# Desklamp_H180804_V1.net
KiCad netlist of a schematic drawn in EAGLE
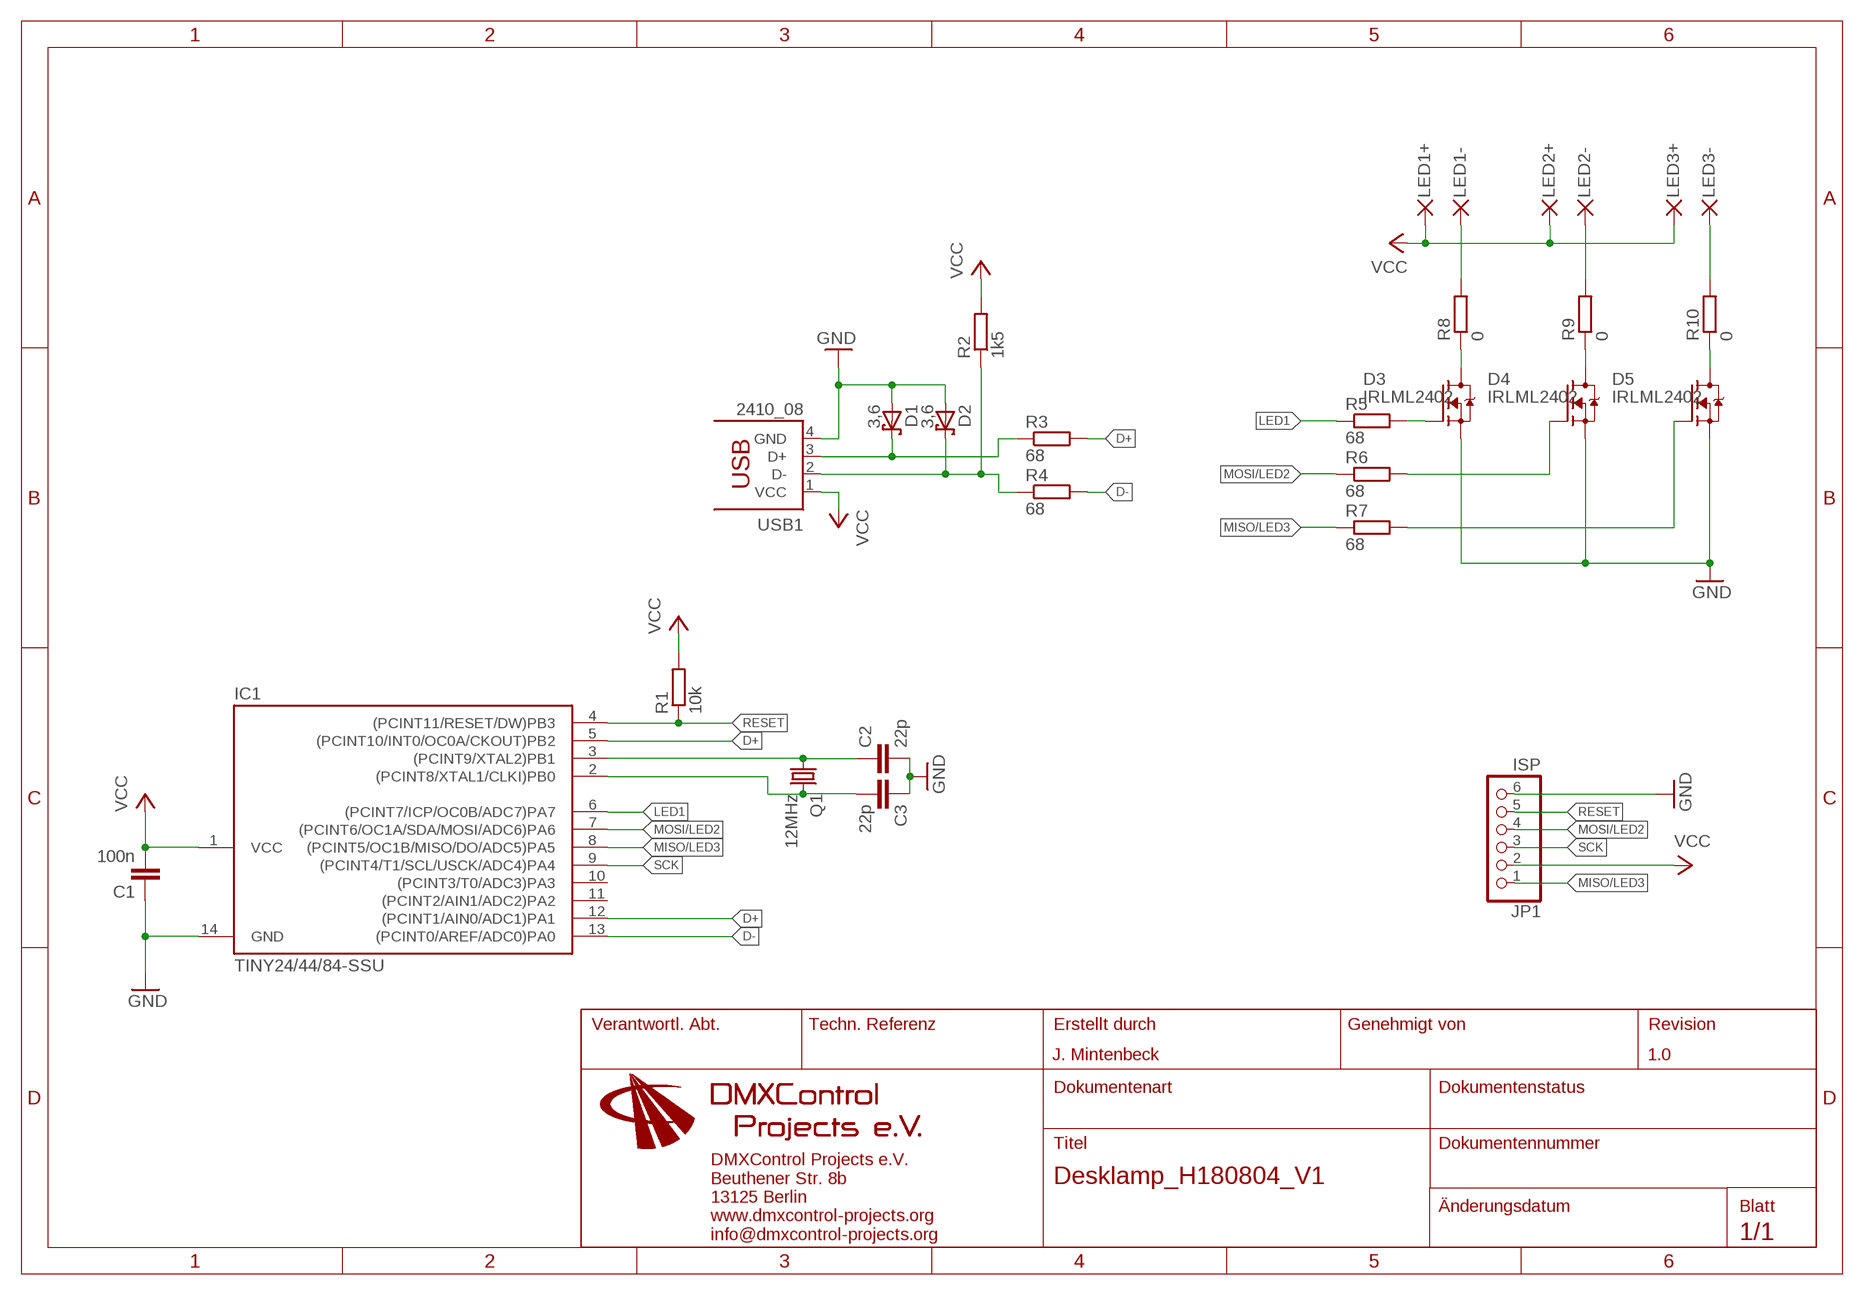
[diagram p0: schematic, sheet 1]

(export (version "E")
  (design (tool "Eeschema 10.0.6"))
  (components
    (comp (ref "C1")
      (value "100n")
      (footprint "eagle-import:C0805")
      (fields (field (name "PARTNO") "CC0805KRX7R9BB104"))
      (libsource (lib "eagle-import") (part "C-EUC0805"))
    )
    (comp (ref "C2")
      (value "22p")
      (footprint "eagle-import:C0805")
      (fields (field (name "PARTNO") "VVS-SMD COG 50 V 22 PF G0805"))
      (libsource (lib "eagle-import") (part "C-EUC0805"))
    )
    (comp (ref "C3")
      (value "22p")
      (footprint "eagle-import:C0805")
      (fields (field (name "PARTNO") "VVS-SMD COG 50 V 22 PF G0805"))
      (libsource (lib "eagle-import") (part "C-EUC0805"))
    )
    (comp (ref "D1")
      (value "3,6")
      (footprint "eagle-import:SOT23")
      (fields (field (name "PARTNO") "BZX84C3V6"))
      (libsource (lib "eagle-import") (part "BAS40"))
    )
    (comp (ref "D2")
      (value "3,6")
      (footprint "eagle-import:SOT23")
      (fields (field (name "PARTNO") "BZX84C3V6"))
      (libsource (lib "eagle-import") (part "BAS40"))
    )
    (comp (ref "D3")
      (value "IRLML2402")
      (footprint "eagle-import:SOT23")
      (fields (field (name "PARTNO") "IRLML2402PBF"))
      (libsource (lib "eagle-import") (part "IRLML2402"))
    )
    (comp (ref "D4")
      (value "IRLML2402")
      (footprint "eagle-import:SOT23")
      (fields (field (name "PARTNO") "IRLML2402PBF"))
      (libsource (lib "eagle-import") (part "IRLML2402"))
    )
    (comp (ref "D5")
      (value "IRLML2402")
      (footprint "eagle-import:SOT23")
      (fields (field (name "PARTNO") "IRLML2402PBF"))
      (libsource (lib "eagle-import") (part "IRLML2402"))
    )
    (comp (ref "IC1")
      (value "TINY24/44/84-SSU")
      (footprint "eagle-import:SOIC14")
      (fields (field (name "PARTNO") "ATTINY44ASSU"))
      (libsource (lib "eagle-import") (part "TINY24/44/84-SSU"))
    )
    (comp (ref "JP1")
      (value "ISP")
      (footprint "eagle-import:1X06M")
      (libsource (lib "eagle-import") (part "PINHD-1X06_2.00"))
    )
    (comp (ref "PAD1")
      (value "LED1+")
      (footprint "eagle-import:SMD1,27-2,54")
      (libsource (lib "eagle-import") (part "SMD2"))
    )
    (comp (ref "PAD2")
      (value "LED1-")
      (footprint "eagle-import:SMD1,27-2,54")
      (libsource (lib "eagle-import") (part "SMD2"))
    )
    (comp (ref "PAD3")
      (value "LED2+")
      (footprint "eagle-import:SMD1,27-2,54")
      (libsource (lib "eagle-import") (part "SMD2"))
    )
    (comp (ref "PAD4")
      (value "LED2-")
      (footprint "eagle-import:SMD1,27-2,54")
      (libsource (lib "eagle-import") (part "SMD2"))
    )
    (comp (ref "PAD5")
      (value "LED3+")
      (footprint "eagle-import:SMD1,27-2,54")
      (libsource (lib "eagle-import") (part "SMD2"))
    )
    (comp (ref "PAD6")
      (value "LED3-")
      (footprint "eagle-import:SMD1,27-2,54")
      (libsource (lib "eagle-import") (part "SMD2"))
    )
    (comp (ref "Q1")
      (value "12MHz")
      (footprint "eagle-import:HC49UP")
      (fields (field (name "PARTNO") "12.000MHZ 49USMX/30/50/40/18PF/ATF"))
      (libsource (lib "eagle-import") (part "CRYSTALHC49UP"))
    )
    (comp (ref "R1")
      (value "10k")
      (footprint "eagle-import:R0805")
      (fields (field (name "PARTNO") "RC0805 FR-07 10 K"))
      (libsource (lib "eagle-import") (part "R-EU_R0805"))
    )
    (comp (ref "R2")
      (value "1k5")
      (footprint "eagle-import:R0805")
      (fields (field (name "PARTNO") "RC0805 FR-07 1,5 K"))
      (libsource (lib "eagle-import") (part "R-EU_R0805"))
    )
    (comp (ref "R3")
      (value "68")
      (footprint "eagle-import:R0805")
      (fields (field (name "PARTNO") "RC0805 FR-07 68 R"))
      (libsource (lib "eagle-import") (part "R-EU_R0805"))
    )
    (comp (ref "R4")
      (value "68")
      (footprint "eagle-import:R0805")
      (fields (field (name "PARTNO") "RC0805 FR-07 68 R"))
      (libsource (lib "eagle-import") (part "R-EU_R0805"))
    )
    (comp (ref "R5")
      (value "68")
      (footprint "eagle-import:R0805")
      (fields (field (name "PARTNO") "RC0805 FR-07 68 R"))
      (libsource (lib "eagle-import") (part "R-EU_R0805"))
    )
    (comp (ref "R6")
      (value "68")
      (footprint "eagle-import:R0805")
      (fields (field (name "PARTNO") "RC0805 FR-07 68 R"))
      (libsource (lib "eagle-import") (part "R-EU_R0805"))
    )
    (comp (ref "R7")
      (value "68")
      (footprint "eagle-import:R0805")
      (fields (field (name "PARTNO") "RC0805 FR-07 68 R"))
      (libsource (lib "eagle-import") (part "R-EU_R0805"))
    )
    (comp (ref "R8")
      (value "0")
      (footprint "eagle-import:R0805")
      (fields (field (name "PARTNO") "RC0805 FR-07 0 R"))
      (libsource (lib "eagle-import") (part "R-EU_R0805"))
    )
    (comp (ref "R9")
      (value "0")
      (footprint "eagle-import:R0805")
      (fields (field (name "PARTNO") "RC0805 FR-07 0 R"))
      (libsource (lib "eagle-import") (part "R-EU_R0805"))
    )
    (comp (ref "R10")
      (value "0")
      (footprint "eagle-import:R0805")
      (fields (field (name "PARTNO") "RC0805 FR-07 0 R"))
      (libsource (lib "eagle-import") (part "R-EU_R0805"))
    )
    (comp (ref "USB1")
      (value "2410_08")
      (footprint "eagle-import:2410_08")
      (fields (field (name "PARTNO") "2410 08"))
      (libsource (lib "eagle-import") (part "2410_08"))
    )
  )
  (nets
    (net (code "1") (name "D+") (class "Default")
      (node (ref "IC1") (pin "12") (pinfunction "(PCINT1/AIN0/ADC1)PA1_12") (pintype "bidirectional"))
      (node (ref "IC1") (pin "5") (pinfunction "(PCINT10/INT0/OC0A/CKOUT)PB2_5") (pintype "bidirectional"))
      (node (ref "R3") (pin "2") (pinfunction "2_2") (pintype "passive"))
    )
    (net (code "2") (name "D-") (class "Default")
      (node (ref "IC1") (pin "13") (pinfunction "(PCINT0/AREF/ADC0)PA0_13") (pintype "bidirectional"))
      (node (ref "R4") (pin "2") (pinfunction "2_2") (pintype "passive"))
    )
    (net (code "3") (name "GND") (class "Default")
      (node (ref "C1") (pin "1") (pinfunction "1_1") (pintype "passive"))
      (node (ref "C2") (pin "2") (pinfunction "2_2") (pintype "passive"))
      (node (ref "C3") (pin "1") (pinfunction "1_1") (pintype "passive"))
      (node (ref "D1") (pin "1") (pinfunction "A_1") (pintype "passive"))
      (node (ref "D2") (pin "1") (pinfunction "A_1") (pintype "passive"))
      (node (ref "D3") (pin "2") (pinfunction "S_2") (pintype "passive"))
      (node (ref "D4") (pin "2") (pinfunction "S_2") (pintype "passive"))
      (node (ref "D5") (pin "2") (pinfunction "S_2") (pintype "passive"))
      (node (ref "IC1") (pin "14") (pinfunction "GND_14") (pintype "power_in"))
      (node (ref "JP1") (pin "6") (pinfunction "6_6") (pintype "passive"))
      (node (ref "USB1") (pin "4") (pinfunction "GND_4") (pintype "passive"))
    )
    (net (code "4") (name "LED1") (class "Default")
      (node (ref "IC1") (pin "6") (pinfunction "(PCINT7/ICP/OC0B/ADC7)PA7_6") (pintype "bidirectional"))
      (node (ref "R5") (pin "1") (pinfunction "1_1") (pintype "passive"))
    )
    (net (code "5") (name "MISO{slash}LED3") (class "Default")
      (node (ref "IC1") (pin "8") (pinfunction "(PCINT5/OC1B/MISO/DO/ADC5)PA5_8") (pintype "bidirectional"))
      (node (ref "JP1") (pin "1") (pinfunction "1_1") (pintype "passive"))
      (node (ref "R7") (pin "1") (pinfunction "1_1") (pintype "passive"))
    )
    (net (code "6") (name "MOSI{slash}LED2") (class "Default")
      (node (ref "IC1") (pin "7") (pinfunction "(PCINT6/OC1A/SDA/MOSI/ADC6)PA6_7") (pintype "bidirectional"))
      (node (ref "JP1") (pin "4") (pinfunction "4_4") (pintype "passive"))
      (node (ref "R6") (pin "1") (pinfunction "1_1") (pintype "passive"))
    )
    (net (code "7") (name "Net-(D1-C)") (class "Default")
      (node (ref "D1") (pin "3") (pinfunction "C_3") (pintype "passive"))
      (node (ref "R3") (pin "1") (pinfunction "1_1") (pintype "passive"))
      (node (ref "USB1") (pin "3") (pinfunction "D+_3") (pintype "passive"))
    )
    (net (code "8") (name "Net-(D2-C)") (class "Default")
      (node (ref "D2") (pin "3") (pinfunction "C_3") (pintype "passive"))
      (node (ref "R2") (pin "1") (pinfunction "1_1") (pintype "passive"))
      (node (ref "R4") (pin "1") (pinfunction "1_1") (pintype "passive"))
      (node (ref "USB1") (pin "2") (pinfunction "D-_2") (pintype "passive"))
    )
    (net (code "9") (name "Net-(D3-D)") (class "Default")
      (node (ref "D3") (pin "3") (pinfunction "D_3") (pintype "passive"))
      (node (ref "R8") (pin "1") (pinfunction "1_1") (pintype "passive"))
    )
    (net (code "10") (name "Net-(D3-G)") (class "Default")
      (node (ref "D3") (pin "1") (pinfunction "G_1") (pintype "passive"))
      (node (ref "R5") (pin "2") (pinfunction "2_2") (pintype "passive"))
    )
    (net (code "11") (name "Net-(D4-D)") (class "Default")
      (node (ref "D4") (pin "3") (pinfunction "D_3") (pintype "passive"))
      (node (ref "R9") (pin "1") (pinfunction "1_1") (pintype "passive"))
    )
    (net (code "12") (name "Net-(D4-G)") (class "Default")
      (node (ref "D4") (pin "1") (pinfunction "G_1") (pintype "passive"))
      (node (ref "R6") (pin "2") (pinfunction "2_2") (pintype "passive"))
    )
    (net (code "13") (name "Net-(D5-D)") (class "Default")
      (node (ref "D5") (pin "3") (pinfunction "D_3") (pintype "passive"))
      (node (ref "R10") (pin "1") (pinfunction "1_1") (pintype "passive"))
    )
    (net (code "14") (name "Net-(D5-G)") (class "Default")
      (node (ref "D5") (pin "1") (pinfunction "G_1") (pintype "passive"))
      (node (ref "R7") (pin "2") (pinfunction "2_2") (pintype "passive"))
    )
    (net (code "15") (name "Net-(IC1-(PCINT8{slash}XTAL1{slash}CLKI)PB0)") (class "Default")
      (node (ref "C3") (pin "2") (pinfunction "2_2") (pintype "passive"))
      (node (ref "IC1") (pin "2") (pinfunction "(PCINT8/XTAL1/CLKI)PB0_2") (pintype "bidirectional"))
      (node (ref "Q1") (pin "2") (pinfunction "2_2") (pintype "passive"))
    )
    (net (code "16") (name "Net-(IC1-(PCINT9{slash}XTAL2)PB1)") (class "Default")
      (node (ref "C2") (pin "1") (pinfunction "1_1") (pintype "passive"))
      (node (ref "IC1") (pin "3") (pinfunction "(PCINT9/XTAL2)PB1_3") (pintype "bidirectional"))
      (node (ref "Q1") (pin "1") (pinfunction "1_1") (pintype "passive"))
    )
    (net (code "17") (name "Net-(PAD2-P)") (class "Default")
      (node (ref "PAD2") (pin "1") (pinfunction "P_1") (pintype "passive"))
      (node (ref "R8") (pin "2") (pinfunction "2_2") (pintype "passive"))
    )
    (net (code "18") (name "Net-(PAD4-P)") (class "Default")
      (node (ref "PAD4") (pin "1") (pinfunction "P_1") (pintype "passive"))
      (node (ref "R9") (pin "2") (pinfunction "2_2") (pintype "passive"))
    )
    (net (code "19") (name "Net-(PAD6-P)") (class "Default")
      (node (ref "PAD6") (pin "1") (pinfunction "P_1") (pintype "passive"))
      (node (ref "R10") (pin "2") (pinfunction "2_2") (pintype "passive"))
    )
    (net (code "20") (name "RESET") (class "Default")
      (node (ref "IC1") (pin "4") (pinfunction "(PCINT11/RESET/DW)PB3_4") (pintype "bidirectional"))
      (node (ref "JP1") (pin "5") (pinfunction "5_5") (pintype "passive"))
      (node (ref "R1") (pin "1") (pinfunction "1_1") (pintype "passive"))
    )
    (net (code "21") (name "SCK") (class "Default")
      (node (ref "IC1") (pin "9") (pinfunction "(PCINT4/T1/SCL/USCK/ADC4)PA4_9") (pintype "bidirectional"))
      (node (ref "JP1") (pin "3") (pinfunction "3_3") (pintype "passive"))
    )
    (net (code "22") (name "VCC") (class "Default")
      (node (ref "C1") (pin "2") (pinfunction "2_2") (pintype "passive"))
      (node (ref "IC1") (pin "1") (pinfunction "VCC_1") (pintype "power_in"))
      (node (ref "JP1") (pin "2") (pinfunction "2_2") (pintype "passive"))
      (node (ref "PAD1") (pin "1") (pinfunction "P_1") (pintype "passive"))
      (node (ref "PAD3") (pin "1") (pinfunction "P_1") (pintype "passive"))
      (node (ref "PAD5") (pin "1") (pinfunction "P_1") (pintype "passive"))
      (node (ref "R1") (pin "2") (pinfunction "2_2") (pintype "passive"))
      (node (ref "R2") (pin "2") (pinfunction "2_2") (pintype "passive"))
      (node (ref "USB1") (pin "1") (pinfunction "VCC_1") (pintype "passive"))
    )
    (net (code "23") (name "unconnected-(IC1-(PCINT2{slash}AIN1{slash}ADC2)PA2-Pad11)") (class "Default")
      (node (ref "IC1") (pin "11") (pinfunction "(PCINT2/AIN1/ADC2)PA2_11") (pintype "bidirectional"))
    )
    (net (code "24") (name "unconnected-(IC1-(PCINT3{slash}T0{slash}ADC3)PA3-Pad10)") (class "Default")
      (node (ref "IC1") (pin "10") (pinfunction "(PCINT3/T0/ADC3)PA3_10") (pintype "bidirectional"))
    )
  )
)
